# INVERTER.net
KiCad netlist of a schematic drawn in EAGLE
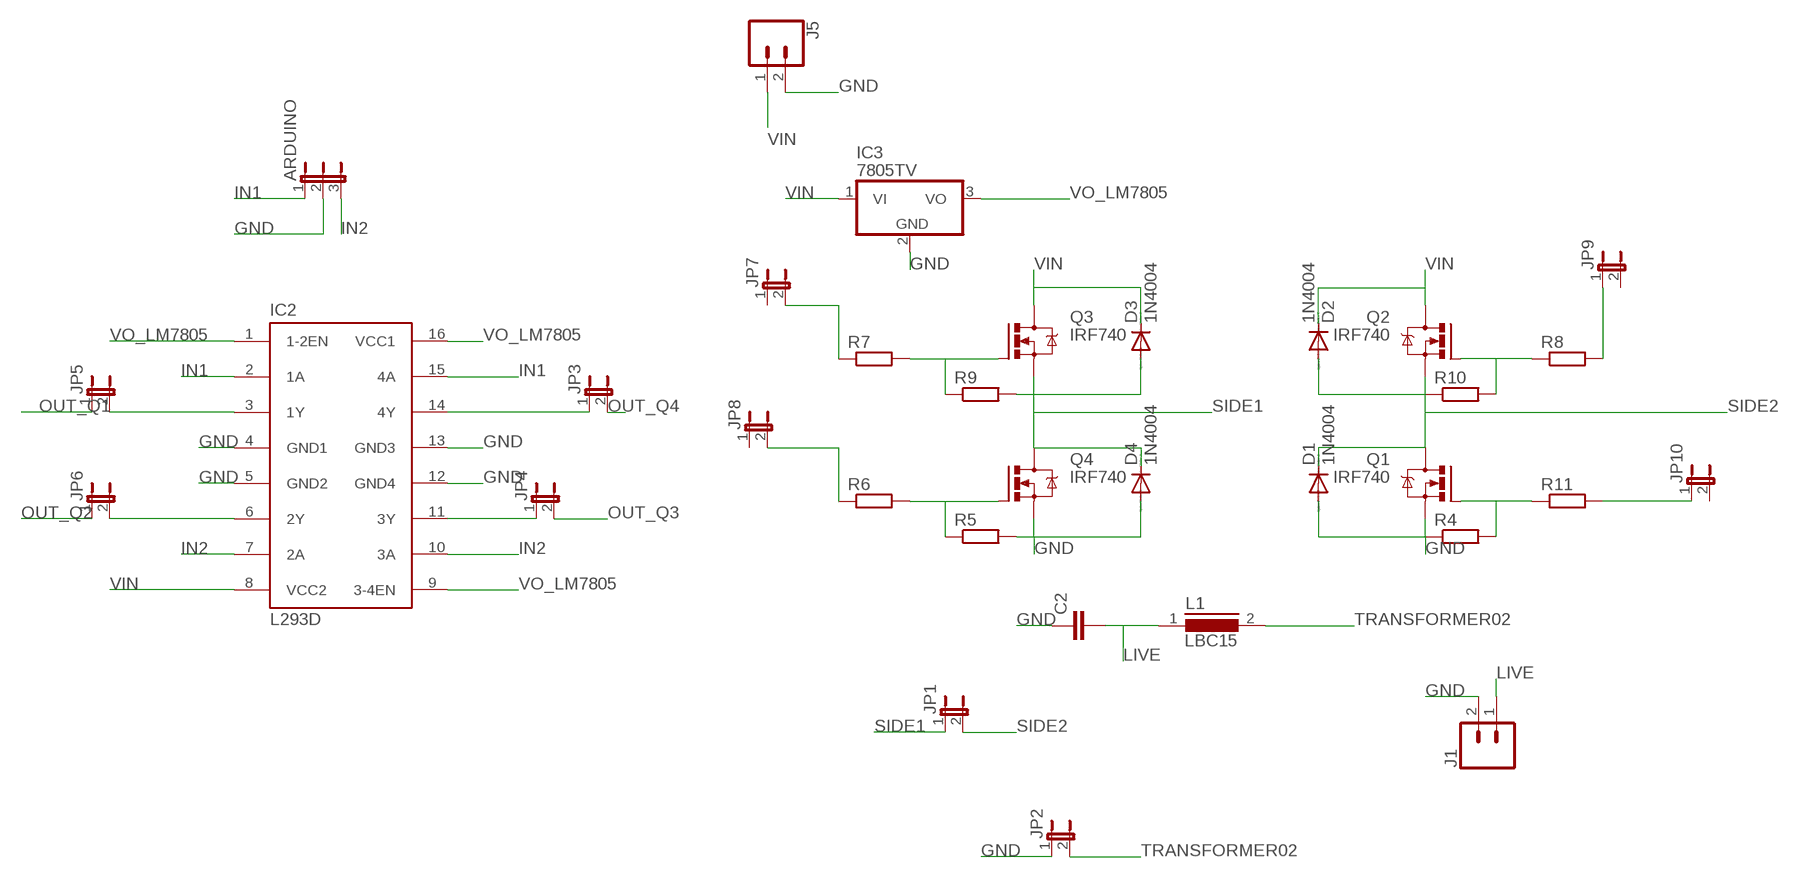
[diagram p0: schematic, sheet 1]

(export (version "E")
  (design (tool "Eeschema 10.0.6"))
  (components
    (comp (ref "ARDUINO")
      (value "JP2E")
      (footprint "eagle-import:JP2")
      (libsource (lib "eagle-import") (part "JP2E"))
    )
    (comp (ref "C2")
      (value "C5/5.5")
      (footprint "eagle-import:C5B5.5")
      (libsource (lib "eagle-import") (part "C5/5.5"))
    )
    (comp (ref "D1")
      (value "1N4004")
      (footprint "eagle-import:DO41-10")
      (libsource (lib "eagle-import") (part "1N4004"))
    )
    (comp (ref "D2")
      (value "1N4004")
      (footprint "eagle-import:DO41-10")
      (libsource (lib "eagle-import") (part "1N4004"))
    )
    (comp (ref "D3")
      (value "1N4004")
      (footprint "eagle-import:DO41-10")
      (libsource (lib "eagle-import") (part "1N4004"))
    )
    (comp (ref "D4")
      (value "1N4004")
      (footprint "eagle-import:DO41-10")
      (libsource (lib "eagle-import") (part "1N4004"))
    )
    (comp (ref "IC2")
      (value "L293D")
      (footprint "eagle-import:DIL16")
      (libsource (lib "eagle-import") (part "L293D"))
    )
    (comp (ref "IC3")
      (value "7805TV")
      (footprint "eagle-import:TO220V")
      (libsource (lib "eagle-import") (part "78TV05"))
    )
    (comp (ref "J1")
      (value "CONN_02PTH4")
      (footprint "eagle-import:1X02_XTRA_BIG")
      (libsource (lib "eagle-import") (part "CONN_02PTH4"))
    )
    (comp (ref "J5")
      (value "CONN_02PTH4")
      (footprint "eagle-import:1X02_XTRA_BIG")
      (libsource (lib "eagle-import") (part "CONN_02PTH4"))
    )
    (comp (ref "JP1")
      (value "JP1E")
      (footprint "eagle-import:JP1")
      (libsource (lib "eagle-import") (part "JP1E"))
    )
    (comp (ref "JP2")
      (value "JP1E")
      (footprint "eagle-import:JP1")
      (libsource (lib "eagle-import") (part "JP1E"))
    )
    (comp (ref "JP3")
      (value "JP1E")
      (footprint "eagle-import:JP1")
      (libsource (lib "eagle-import") (part "JP1E"))
    )
    (comp (ref "JP4")
      (value "JP1E")
      (footprint "eagle-import:JP1")
      (libsource (lib "eagle-import") (part "JP1E"))
    )
    (comp (ref "JP5")
      (value "JP1E")
      (footprint "eagle-import:JP1")
      (libsource (lib "eagle-import") (part "JP1E"))
    )
    (comp (ref "JP6")
      (value "JP1E")
      (footprint "eagle-import:JP1")
      (libsource (lib "eagle-import") (part "JP1E"))
    )
    (comp (ref "JP7")
      (value "JP1E")
      (footprint "eagle-import:JP1")
      (libsource (lib "eagle-import") (part "JP1E"))
    )
    (comp (ref "JP8")
      (value "JP1E")
      (footprint "eagle-import:JP1")
      (libsource (lib "eagle-import") (part "JP1E"))
    )
    (comp (ref "JP9")
      (value "JP1E")
      (footprint "eagle-import:JP1")
      (libsource (lib "eagle-import") (part "JP1E"))
    )
    (comp (ref "JP10")
      (value "JP1E")
      (footprint "eagle-import:JP1")
      (libsource (lib "eagle-import") (part "JP1E"))
    )
    (comp (ref "L1")
      (value "LBC15")
      (footprint "eagle-import:LBC15")
      (libsource (lib "eagle-import") (part "LBC15"))
    )
    (comp (ref "Q1")
      (value "IRF740")
      (footprint "eagle-import:TO220BV")
      (libsource (lib "eagle-import") (part "IRF740"))
    )
    (comp (ref "Q2")
      (value "IRF740")
      (footprint "eagle-import:TO220BV")
      (libsource (lib "eagle-import") (part "IRF740"))
    )
    (comp (ref "Q3")
      (value "IRF740")
      (footprint "eagle-import:TO220BV")
      (libsource (lib "eagle-import") (part "IRF740"))
    )
    (comp (ref "Q4")
      (value "IRF740")
      (footprint "eagle-import:TO220BV")
      (libsource (lib "eagle-import") (part "IRF740"))
    )
    (comp (ref "R4")
      (value "R-EU_VMTA55")
      (footprint "eagle-import:VMTA55")
      (libsource (lib "eagle-import") (part "R-EU_VMTA55"))
    )
    (comp (ref "R5")
      (value "R-EU_VMTA55")
      (footprint "eagle-import:VMTA55")
      (libsource (lib "eagle-import") (part "R-EU_VMTA55"))
    )
    (comp (ref "R6")
      (value "R-EU_VMTA55")
      (footprint "eagle-import:VMTA55")
      (libsource (lib "eagle-import") (part "R-EU_VMTA55"))
    )
    (comp (ref "R7")
      (value "R-EU_VMTA55")
      (footprint "eagle-import:VMTA55")
      (libsource (lib "eagle-import") (part "R-EU_VMTA55"))
    )
    (comp (ref "R8")
      (value "R-EU_VMTA55")
      (footprint "eagle-import:VMTA55")
      (libsource (lib "eagle-import") (part "R-EU_VMTA55"))
    )
    (comp (ref "R9")
      (value "R-EU_VMTA55")
      (footprint "eagle-import:VMTA55")
      (libsource (lib "eagle-import") (part "R-EU_VMTA55"))
    )
    (comp (ref "R10")
      (value "R-EU_VMTA55")
      (footprint "eagle-import:VMTA55")
      (libsource (lib "eagle-import") (part "R-EU_VMTA55"))
    )
    (comp (ref "R11")
      (value "R-EU_VMTA55")
      (footprint "eagle-import:VMTA55")
      (libsource (lib "eagle-import") (part "R-EU_VMTA55"))
    )
  )
  (nets
    (net (code "1") (name "/GND") (class "Default")
      (node (ref "ARDUINO") (pin "2") (pinfunction "2_2") (pintype "passive"))
      (node (ref "C2") (pin "1") (pinfunction "1_1") (pintype "passive"))
      (node (ref "D1") (pin "A") (pinfunction "A_A") (pintype "passive"))
      (node (ref "D4") (pin "A") (pinfunction "A_A") (pintype "passive"))
      (node (ref "IC2") (pin "12") (pinfunction "GND4_12") (pintype "power_in"))
      (node (ref "IC2") (pin "13") (pinfunction "GND3_13") (pintype "power_in"))
      (node (ref "IC2") (pin "4") (pinfunction "GND1_4") (pintype "power_in"))
      (node (ref "IC2") (pin "5") (pinfunction "GND2_5") (pintype "power_in"))
      (node (ref "IC3") (pin "2") (pinfunction "GND_2") (pintype "passive"))
      (node (ref "J1") (pin "2") (pinfunction "2_2") (pintype "passive"))
      (node (ref "J5") (pin "2") (pinfunction "2_2") (pintype "passive"))
      (node (ref "JP2") (pin "1") (pinfunction "1_1") (pintype "passive"))
      (node (ref "Q1") (pin "S") (pinfunction "S_S") (pintype "passive"))
      (node (ref "Q4") (pin "S") (pinfunction "S_S") (pintype "passive"))
      (node (ref "R4") (pin "1") (pinfunction "1_1") (pintype "passive"))
      (node (ref "R5") (pin "2") (pinfunction "2_2") (pintype "passive"))
    )
    (net (code "2") (name "/IN1") (class "Default")
      (node (ref "ARDUINO") (pin "1") (pinfunction "1_1") (pintype "passive"))
      (node (ref "IC2") (pin "15") (pinfunction "4A_15") (pintype "input"))
      (node (ref "IC2") (pin "2") (pinfunction "1A_2") (pintype "input"))
    )
    (net (code "3") (name "/IN2") (class "Default")
      (node (ref "ARDUINO") (pin "3") (pinfunction "3_3") (pintype "passive"))
      (node (ref "IC2") (pin "10") (pinfunction "3A_10") (pintype "input"))
      (node (ref "IC2") (pin "7") (pinfunction "2A_7") (pintype "input"))
    )
    (net (code "4") (name "/LIVE") (class "Default")
      (node (ref "C2") (pin "2") (pinfunction "2_2") (pintype "passive"))
      (node (ref "J1") (pin "1") (pinfunction "1_1") (pintype "passive"))
      (node (ref "L1") (pin "1") (pinfunction "1_1") (pintype "passive"))
    )
    (net (code "5") (name "/OUT_Q1") (class "Default")
      (node (ref "JP5") (pin "1") (pinfunction "1_1") (pintype "passive"))
    )
    (net (code "6") (name "/OUT_Q2") (class "Default")
      (node (ref "JP6") (pin "1") (pinfunction "1_1") (pintype "passive"))
    )
    (net (code "7") (name "/OUT_Q3") (class "Default")
      (node (ref "JP4") (pin "2") (pinfunction "2_2") (pintype "passive"))
    )
    (net (code "8") (name "/OUT_Q4") (class "Default")
      (node (ref "JP3") (pin "2") (pinfunction "2_2") (pintype "passive"))
    )
    (net (code "9") (name "/SIDE1") (class "Default")
      (node (ref "D3") (pin "A") (pinfunction "A_A") (pintype "passive"))
      (node (ref "D4") (pin "C") (pinfunction "C_C") (pintype "passive"))
      (node (ref "JP1") (pin "1") (pinfunction "1_1") (pintype "passive"))
      (node (ref "Q3") (pin "S") (pinfunction "S_S") (pintype "passive"))
      (node (ref "Q4") (pin "D") (pinfunction "D_D") (pintype "passive"))
      (node (ref "R9") (pin "2") (pinfunction "2_2") (pintype "passive"))
    )
    (net (code "10") (name "/SIDE2") (class "Default")
      (node (ref "D1") (pin "C") (pinfunction "C_C") (pintype "passive"))
      (node (ref "D2") (pin "A") (pinfunction "A_A") (pintype "passive"))
      (node (ref "JP1") (pin "2") (pinfunction "2_2") (pintype "passive"))
      (node (ref "Q1") (pin "D") (pinfunction "D_D") (pintype "passive"))
      (node (ref "Q2") (pin "S") (pinfunction "S_S") (pintype "passive"))
      (node (ref "R10") (pin "1") (pinfunction "1_1") (pintype "passive"))
    )
    (net (code "11") (name "/TRANSFORMER02") (class "Default")
      (node (ref "JP2") (pin "2") (pinfunction "2_2") (pintype "passive"))
      (node (ref "L1") (pin "2") (pinfunction "2_2") (pintype "passive"))
    )
    (net (code "12") (name "/VIN") (class "Default")
      (node (ref "D2") (pin "C") (pinfunction "C_C") (pintype "passive"))
      (node (ref "D3") (pin "C") (pinfunction "C_C") (pintype "passive"))
      (node (ref "IC2") (pin "8") (pinfunction "VCC2_8") (pintype "power_in"))
      (node (ref "IC3") (pin "1") (pinfunction "VI_1") (pintype "input"))
      (node (ref "J5") (pin "1") (pinfunction "1_1") (pintype "passive"))
      (node (ref "Q2") (pin "D") (pinfunction "D_D") (pintype "passive"))
      (node (ref "Q3") (pin "D") (pinfunction "D_D") (pintype "passive"))
    )
    (net (code "13") (name "/VO_LM7805") (class "Default")
      (node (ref "IC2") (pin "1") (pinfunction "1-2EN_1") (pintype "input"))
      (node (ref "IC2") (pin "16") (pinfunction "VCC1_16") (pintype "power_in"))
      (node (ref "IC2") (pin "9") (pinfunction "3-4EN_9") (pintype "input"))
      (node (ref "IC3") (pin "3") (pinfunction "VO_3") (pintype "passive"))
    )
    (net (code "14") (name "Net-(IC2-1Y)") (class "Default")
      (node (ref "IC2") (pin "3") (pinfunction "1Y_3") (pintype "output"))
      (node (ref "JP5") (pin "2") (pinfunction "2_2") (pintype "passive"))
    )
    (net (code "15") (name "Net-(IC2-2Y)") (class "Default")
      (node (ref "IC2") (pin "6") (pinfunction "2Y_6") (pintype "output"))
      (node (ref "JP6") (pin "2") (pinfunction "2_2") (pintype "passive"))
    )
    (net (code "16") (name "Net-(IC2-3Y)") (class "Default")
      (node (ref "IC2") (pin "11") (pinfunction "3Y_11") (pintype "output"))
      (node (ref "JP4") (pin "1") (pinfunction "1_1") (pintype "passive"))
    )
    (net (code "17") (name "Net-(IC2-4Y)") (class "Default")
      (node (ref "IC2") (pin "14") (pinfunction "4Y_14") (pintype "output"))
      (node (ref "JP3") (pin "1") (pinfunction "1_1") (pintype "passive"))
    )
    (net (code "18") (name "Net-(JP7-Pad2)") (class "Default")
      (node (ref "JP7") (pin "2") (pinfunction "2_2") (pintype "passive"))
      (node (ref "R7") (pin "1") (pinfunction "1_1") (pintype "passive"))
    )
    (net (code "19") (name "Net-(JP8-Pad2)") (class "Default")
      (node (ref "JP8") (pin "2") (pinfunction "2_2") (pintype "passive"))
      (node (ref "R6") (pin "1") (pinfunction "1_1") (pintype "passive"))
    )
    (net (code "20") (name "Net-(JP9-Pad1)") (class "Default")
      (node (ref "JP9") (pin "1") (pinfunction "1_1") (pintype "passive"))
      (node (ref "R8") (pin "2") (pinfunction "2_2") (pintype "passive"))
    )
    (net (code "21") (name "Net-(JP10-Pad1)") (class "Default")
      (node (ref "JP10") (pin "1") (pinfunction "1_1") (pintype "passive"))
      (node (ref "R11") (pin "2") (pinfunction "2_2") (pintype "passive"))
    )
    (net (code "22") (name "Net-(Q1-PadG)") (class "Default")
      (node (ref "Q1") (pin "G") (pinfunction "G_G") (pintype "passive"))
      (node (ref "R11") (pin "1") (pinfunction "1_1") (pintype "passive"))
      (node (ref "R4") (pin "2") (pinfunction "2_2") (pintype "passive"))
    )
    (net (code "23") (name "Net-(Q2-PadG)") (class "Default")
      (node (ref "Q2") (pin "G") (pinfunction "G_G") (pintype "passive"))
      (node (ref "R10") (pin "2") (pinfunction "2_2") (pintype "passive"))
      (node (ref "R8") (pin "1") (pinfunction "1_1") (pintype "passive"))
    )
    (net (code "24") (name "Net-(Q3-PadG)") (class "Default")
      (node (ref "Q3") (pin "G") (pinfunction "G_G") (pintype "passive"))
      (node (ref "R7") (pin "2") (pinfunction "2_2") (pintype "passive"))
      (node (ref "R9") (pin "1") (pinfunction "1_1") (pintype "passive"))
    )
    (net (code "25") (name "Net-(Q4-PadG)") (class "Default")
      (node (ref "Q4") (pin "G") (pinfunction "G_G") (pintype "passive"))
      (node (ref "R5") (pin "1") (pinfunction "1_1") (pintype "passive"))
      (node (ref "R6") (pin "2") (pinfunction "2_2") (pintype "passive"))
    )
    (net (code "26") (name "unconnected-(JP7-Pad1)") (class "Default")
      (node (ref "JP7") (pin "1") (pinfunction "1_1") (pintype "passive"))
    )
    (net (code "27") (name "unconnected-(JP8-Pad1)") (class "Default")
      (node (ref "JP8") (pin "1") (pinfunction "1_1") (pintype "passive"))
    )
    (net (code "28") (name "unconnected-(JP9-Pad2)") (class "Default")
      (node (ref "JP9") (pin "2") (pinfunction "2_2") (pintype "passive"))
    )
    (net (code "29") (name "unconnected-(JP10-Pad2)") (class "Default")
      (node (ref "JP10") (pin "2") (pinfunction "2_2") (pintype "passive"))
    )
  )
)
